# ESP8266.net
KiCad netlist of a schematic drawn in Altium Designer
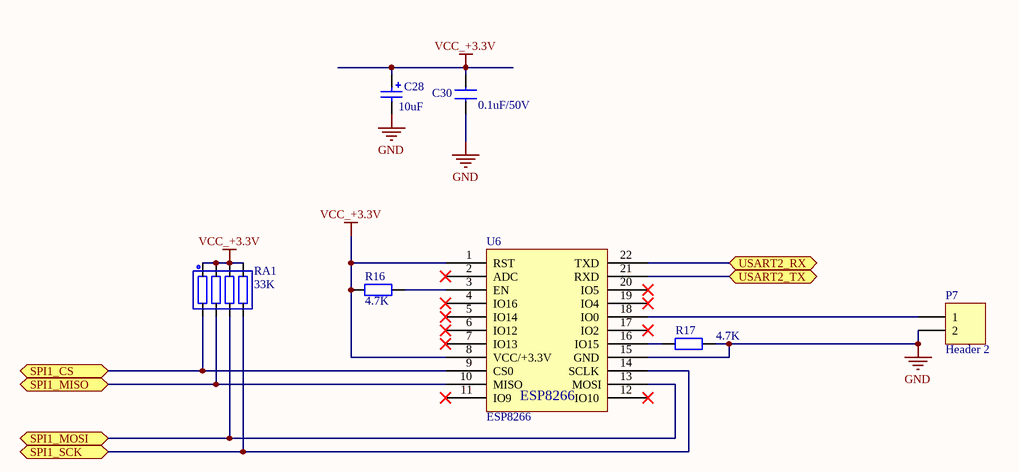
[diagram p0: ESP8266.SchDoc]

(export (version "E")
  (design (tool "Eeschema 10.0.6"))
  (components
    (comp (ref "C28")
      (value "10uF")
      (footprint "CAPTANC")
      (description "Polarized Capacitor (Radial)")
      (fields (field (name "PUBLISHER") "Altium Limited"))
      (libsource (lib "Calf") (part "Cap Pol"))
    )
    (comp (ref "C30") (value "0.1uF/50V") (footprint "0603C") (libsource (lib "0603C") (part "CAP")))
    (comp (ref "P7")
      (value "Header 2")
      (footprint "HDR1*2 - duplicate")
      (description "Header, 2-Pin")
      (fields (field (name "PUBLISHER") "Altium Limited"))
      (libsource (lib "Miscellaneous Connectors") (part "Header 2"))
    )
    (comp (ref "R16") (value "4.7K") (footprint "0603R") (libsource (lib "*") (part "0603R")))
    (comp (ref "R17") (value "4.7K") (footprint "0603R") (libsource (lib "*") (part "0603R")))
    (comp (ref "RA1")
      (value "33K")
      (footprint "RES_PACK_SMD_E")
      (libsource (lib "SCT1212V100") (part "RESPACK4"))
    )
    (comp (ref "U6") (value "ESP8266") (footprint "ESP8266") (libsource (lib "JYModule") (part "ESP8266")))
  )
  (nets
    (net (code "1") (name "/SPI1_CS") (class "Default")
      (node (ref "RA1") (pin "8") (pintype "passive"))
      (node (ref "U6") (pin "9") (pinfunction "CS0_9") (pintype "passive"))
    )
    (net (code "2") (name "/SPI1_MISO") (class "Default")
      (node (ref "RA1") (pin "7") (pintype "passive"))
      (node (ref "U6") (pin "10") (pinfunction "MISO_10") (pintype "passive"))
    )
    (net (code "3") (name "/SPI1_MOSI") (class "Default")
      (node (ref "RA1") (pin "6") (pintype "passive"))
      (node (ref "U6") (pin "13") (pinfunction "MOSI_13") (pintype "passive"))
    )
    (net (code "4") (name "/SPI1_SCK") (class "Default")
      (node (ref "RA1") (pin "5") (pintype "passive"))
      (node (ref "U6") (pin "14") (pinfunction "SCLK_14") (pintype "passive"))
    )
    (net (code "5") (name "/USART2_RX") (class "Default")
      (node (ref "U6") (pin "22") (pinfunction "TXD_22") (pintype "passive"))
    )
    (net (code "6") (name "/USART2_TX") (class "Default")
      (node (ref "U6") (pin "21") (pinfunction "RXD_21") (pintype "passive"))
    )
    (net (code "7") (name "GND") (class "Default")
      (node (ref "C28") (pin "2") (pinfunction "2_2") (pintype "passive"))
      (node (ref "C30") (pin "2") (pinfunction "2_2") (pintype "passive"))
      (node (ref "P7") (pin "2") (pinfunction "2_2") (pintype "passive"))
      (node (ref "R17") (pin "2") (pinfunction "2_2") (pintype "passive"))
      (node (ref "U6") (pin "15") (pinfunction "GND_15") (pintype "passive"))
    )
    (net (code "8") (name "Net-(U6-EN)") (class "Default")
      (node (ref "R16") (pin "2") (pinfunction "2_2") (pintype "passive"))
      (node (ref "U6") (pin "3") (pinfunction "EN_3") (pintype "passive"))
    )
    (net (code "9") (name "Net-(U6-IO0)") (class "Default")
      (node (ref "P7") (pin "1") (pinfunction "1_1") (pintype "passive"))
      (node (ref "U6") (pin "18") (pinfunction "IO0_18") (pintype "passive"))
    )
    (net (code "10") (name "Net-(U6-IO15)") (class "Default")
      (node (ref "R17") (pin "1") (pinfunction "1_1") (pintype "passive"))
      (node (ref "U6") (pin "16") (pinfunction "IO15_16") (pintype "passive"))
    )
    (net (code "11") (name "VCC_+3.3V") (class "Default")
      (node (ref "C28") (pin "1") (pinfunction "1_1") (pintype "passive"))
      (node (ref "C30") (pin "1") (pinfunction "1_1") (pintype "passive"))
      (node (ref "R16") (pin "1") (pinfunction "1_1") (pintype "passive"))
      (node (ref "RA1") (pin "1") (pintype "passive"))
      (node (ref "RA1") (pin "2") (pintype "passive"))
      (node (ref "RA1") (pin "3") (pintype "passive"))
      (node (ref "RA1") (pin "4") (pintype "passive"))
      (node (ref "U6") (pin "1") (pinfunction "RST_1") (pintype "passive"))
      (node (ref "U6") (pin "8") (pinfunction "VCC/+3.3V_8") (pintype "passive"))
    )
    (net (code "12") (name "unconnected-(U6-ADC-Pad2)") (class "Default")
      (node (ref "U6") (pin "2") (pinfunction "ADC_2") (pintype "passive+no_connect"))
    )
    (net (code "13") (name "unconnected-(U6-IO2-Pad17)") (class "Default")
      (node (ref "U6") (pin "17") (pinfunction "IO2_17") (pintype "passive+no_connect"))
    )
    (net (code "14") (name "unconnected-(U6-IO4-Pad19)") (class "Default")
      (node (ref "U6") (pin "19") (pinfunction "IO4_19") (pintype "passive+no_connect"))
    )
    (net (code "15") (name "unconnected-(U6-IO5-Pad20)") (class "Default")
      (node (ref "U6") (pin "20") (pinfunction "IO5_20") (pintype "passive+no_connect"))
    )
    (net (code "16") (name "unconnected-(U6-IO9-Pad11)") (class "Default")
      (node (ref "U6") (pin "11") (pinfunction "IO9_11") (pintype "passive+no_connect"))
    )
    (net (code "17") (name "unconnected-(U6-IO10-Pad12)") (class "Default")
      (node (ref "U6") (pin "12") (pinfunction "IO10_12") (pintype "passive+no_connect"))
    )
    (net (code "18") (name "unconnected-(U6-IO12-Pad6)") (class "Default")
      (node (ref "U6") (pin "6") (pinfunction "IO12_6") (pintype "passive+no_connect"))
    )
    (net (code "19") (name "unconnected-(U6-IO13-Pad7)") (class "Default")
      (node (ref "U6") (pin "7") (pinfunction "IO13_7") (pintype "passive+no_connect"))
    )
    (net (code "20") (name "unconnected-(U6-IO14-Pad5)") (class "Default")
      (node (ref "U6") (pin "5") (pinfunction "IO14_5") (pintype "passive+no_connect"))
    )
    (net (code "21") (name "unconnected-(U6-IO16-Pad4)") (class "Default")
      (node (ref "U6") (pin "4") (pinfunction "IO16_4") (pintype "passive+no_connect"))
    )
  )
)
